# meteo-slave.net
KiCad netlist of a schematic drawn in EAGLE
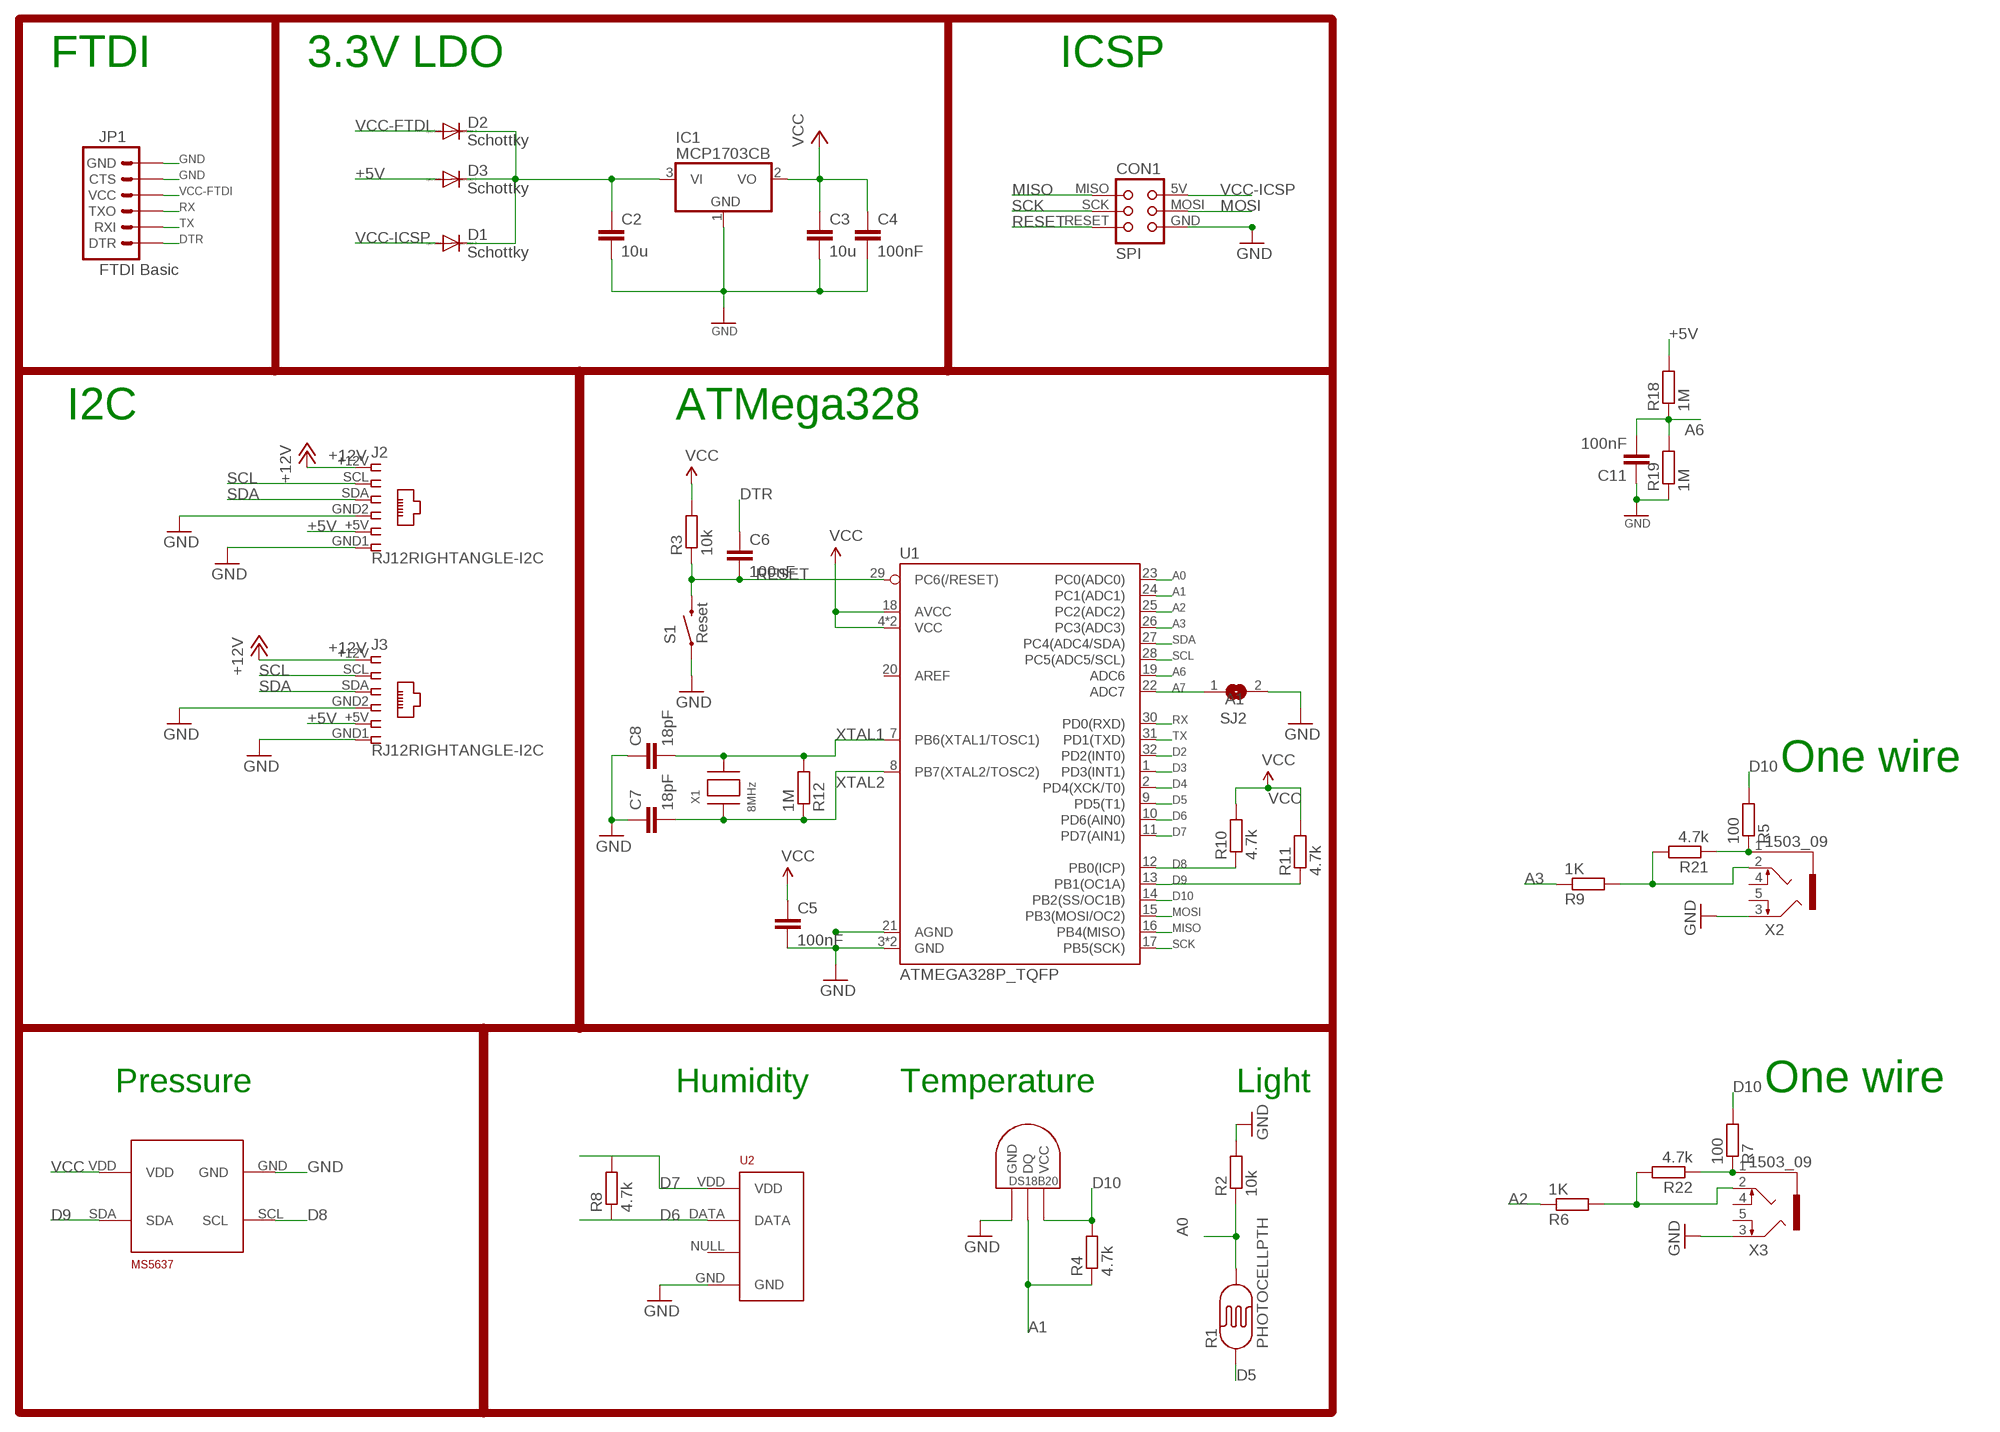
[diagram p0: schematic, sheet 1]

(export (version "E")
  (design (tool "Eeschema 10.0.6"))
  (components
    (comp (ref "C2")
      (value "10u")
      (footprint "eagle-import:C0805K")
      (fields (field (name "MPN") "77-VJ1206V106ZXQTBC"))
      (libsource (lib "eagle-import") (part "C-EUC0805K"))
    )
    (comp (ref "C3")
      (value "10u")
      (footprint "eagle-import:C0805K")
      (fields (field (name "MPN") "77-VJ1206V106ZXQTBC"))
      (libsource (lib "eagle-import") (part "C-EUC0805K"))
    )
    (comp (ref "C4")
      (value "100nF")
      (footprint "eagle-import:C0805K")
      (fields (field (name "MPN") "80-C1206C104K5R"))
      (libsource (lib "eagle-import") (part "C-EUC0805K"))
    )
    (comp (ref "C5")
      (value "100nF")
      (footprint "eagle-import:C0805K")
      (fields (field (name "MPN") "80-C1206C104K5R"))
      (libsource (lib "eagle-import") (part "C-EUC0805K"))
    )
    (comp (ref "C6")
      (value "100nF")
      (footprint "eagle-import:C0805K")
      (fields (field (name "MPN") "80-C1206C104K5R"))
      (libsource (lib "eagle-import") (part "C-EUC0805K"))
    )
    (comp (ref "C7")
      (value "18pF")
      (footprint "eagle-import:C0805K")
      (fields (field (name "MPN") "77-VJ1206A180JXXPBC"))
      (libsource (lib "eagle-import") (part "C-EUC0805K"))
    )
    (comp (ref "C8")
      (value "18pF")
      (footprint "eagle-import:C0805K")
      (fields (field (name "MPN") "77-VJ1206A180JXXPBC"))
      (libsource (lib "eagle-import") (part "C-EUC0805K"))
    )
    (comp (ref "C11")
      (value "100nF")
      (footprint "eagle-import:C0805K")
      (fields (field (name "MPN") "80-C1206C104K5R"))
      (libsource (lib "eagle-import") (part "C-EUC0805K"))
    )
    (comp (ref "CON1")
      (value "SPI")
      (footprint "eagle-import:TC2030-MCP")
      (libsource (lib "eagle-import") (part "TINYISPTAG"))
    )
    (comp (ref "D1")
      (value "Schottky")
      (footprint "eagle-import:SOD123")
      (fields (field (name "MPN") "621-1N5819HW-F"))
      (libsource (lib "eagle-import") (part "MBR0520LT"))
    )
    (comp (ref "D2")
      (value "Schottky")
      (footprint "eagle-import:SOD123")
      (fields (field (name "MPN") "621-1N5819HW-F"))
      (libsource (lib "eagle-import") (part "MBR0520LT"))
    )
    (comp (ref "D3")
      (value "Schottky")
      (footprint "eagle-import:SOD123")
      (fields (field (name "MPN") "621-1N5819HW-F"))
      (libsource (lib "eagle-import") (part "MBR0520LT"))
    )
    (comp (ref "IC1")
      (value "MCP1703CB")
      (footprint "eagle-import:SOT23")
      (libsource (lib "eagle-import") (part "MCP1703CB"))
    )
    (comp (ref "J2")
      (value "RJ12RIGHTANGLE-I2C")
      (footprint "eagle-import:RJ12-RIGHTANGLE-I2C")
      (libsource (lib "eagle-import") (part "RJ12RIGHTANGLE-I2C"))
    )
    (comp (ref "J3")
      (value "RJ12RIGHTANGLE-I2C")
      (footprint "eagle-import:RJ12-RIGHTANGLE-I2C")
      (libsource (lib "eagle-import") (part "RJ12RIGHTANGLE-I2C"))
    )
    (comp (ref "JP1")
      (value "FTDI Basic")
      (footprint "eagle-import:1X06")
      (libsource (lib "eagle-import") (part "ARDUINO_SERIAL_PROGRAMPTH"))
    )
    (comp (ref "R1")
      (value "PHOTOCELLPTH")
      (footprint "eagle-import:PHOTOCELL")
      (libsource (lib "eagle-import") (part "PHOTOCELLPTH"))
    )
    (comp (ref "R2")
      (value "10k")
      (footprint "eagle-import:R0805")
      (libsource (lib "eagle-import") (part "resistor_348_R-EU_R0805"))
    )
    (comp (ref "R3")
      (value "10k")
      (footprint "eagle-import:R0805")
      (libsource (lib "eagle-import") (part "R-EU_R0805"))
    )
    (comp (ref "R4")
      (value "4.7k")
      (footprint "eagle-import:R0805")
      (libsource (lib "eagle-import") (part "resistor_348_R-EU_R0805"))
    )
    (comp (ref "R5")
      (value "100")
      (footprint "eagle-import:R0805")
      (libsource (lib "eagle-import") (part "R-EU_R0805"))
    )
    (comp (ref "R6")
      (value "1K")
      (footprint "eagle-import:R0805")
      (libsource (lib "eagle-import") (part "R-EU_R0805"))
    )
    (comp (ref "R7")
      (value "100")
      (footprint "eagle-import:R0805")
      (libsource (lib "eagle-import") (part "R-EU_R0805"))
    )
    (comp (ref "R8")
      (value "4.7k")
      (footprint "eagle-import:R0805")
      (libsource (lib "eagle-import") (part "resistor_348_R-EU_R0805"))
    )
    (comp (ref "R9")
      (value "1K")
      (footprint "eagle-import:R0805")
      (libsource (lib "eagle-import") (part "R-EU_R0805"))
    )
    (comp (ref "R10")
      (value "4.7k")
      (footprint "eagle-import:R0805")
      (libsource (lib "eagle-import") (part "resistor_348_R-EU_R0805"))
    )
    (comp (ref "R11")
      (value "4.7k")
      (footprint "eagle-import:R0805")
      (libsource (lib "eagle-import") (part "resistor_348_R-EU_R0805"))
    )
    (comp (ref "R12")
      (value "1M")
      (footprint "eagle-import:R0805")
      (libsource (lib "eagle-import") (part "R-EU_R0805"))
    )
    (comp (ref "R18")
      (value "1M")
      (footprint "eagle-import:R0805")
      (libsource (lib "eagle-import") (part "R-EU_R0805"))
    )
    (comp (ref "R19")
      (value "1M")
      (footprint "eagle-import:R0805")
      (libsource (lib "eagle-import") (part "R-EU_R0805"))
    )
    (comp (ref "R21")
      (value "4.7k")
      (footprint "eagle-import:R0805")
      (libsource (lib "eagle-import") (part "resistor_R-EU_R0805"))
    )
    (comp (ref "R22")
      (value "4.7k")
      (footprint "eagle-import:R0805")
      (libsource (lib "eagle-import") (part "resistor_R-EU_R0805"))
    )
    (comp (ref "S1")
      (value "Reset")
      (footprint "eagle-import:TACTILE-SWITCH-SMD-ALT01")
      (libsource (lib "eagle-import") (part "SWITCH-MOMENTARY-2SMD-ALT01"))
    )
    (comp (ref "SJ2") (value "A1") (footprint "eagle-import:SJ") (libsource (lib "eagle-import") (part "SJ")))
    (comp (ref "U$1")
      (value "DS1820TO92")
      (footprint "eagle-import:DS1820")
      (libsource (lib "eagle-import") (part "DS1820TO92"))
    )
    (comp (ref "U$19")
      (value "MS5637WIDE")
      (footprint "eagle-import:MS5637WIDE")
      (libsource (lib "eagle-import") (part "MS5637WIDE"))
    )
    (comp (ref "U1")
      (value "ATMEGA328P_TQFP")
      (footprint "eagle-import:TQFP32-08")
      (libsource (lib "eagle-import") (part "ATMEGA328P_TQFP"))
    )
    (comp (ref "U2")
      (value "RHT03_DHT-22_AM2302")
      (footprint "eagle-import:RHT03_DHT-22")
      (libsource (lib "eagle-import") (part "RHT03_DHT-22_AM2302"))
    )
    (comp (ref "X1")
      (value "8MHz")
      (footprint "eagle-import:NX6035")
      (fields (field (name "MPN") "729-F60800010"))
      (libsource (lib "eagle-import") (part "XTALNX6035"))
    )
    (comp (ref "X2")
      (value "1503_09")
      (footprint "eagle-import:1503_09")
      (libsource (lib "eagle-import") (part "1503_09"))
    )
    (comp (ref "X3")
      (value "1503_09")
      (footprint "eagle-import:1503_09")
      (libsource (lib "eagle-import") (part "1503_09"))
    )
  )
  (nets
    (net (code "1") (name "+5V") (class "Default")
      (node (ref "D3") (pin "A") (pinfunction "A_A") (pintype "passive"))
      (node (ref "J2") (pin "+5V") (pinfunction "5_+5V") (pintype "bidirectional"))
      (node (ref "J3") (pin "+5V") (pinfunction "5_+5V") (pintype "bidirectional"))
      (node (ref "R18") (pin "2") (pinfunction "2_2") (pintype "passive"))
    )
    (net (code "2") (name "+12V") (class "Default")
      (node (ref "J2") (pin "+12V") (pinfunction "1_+12V") (pintype "bidirectional"))
      (node (ref "J3") (pin "+12V") (pinfunction "1_+12V") (pintype "bidirectional"))
    )
    (net (code "3") (name "A0") (class "Default")
      (node (ref "R1") (pin "2") (pinfunction "P$2_2") (pintype "bidirectional"))
      (node (ref "R2") (pin "1") (pinfunction "1_1") (pintype "passive"))
      (node (ref "U1") (pin "23") (pinfunction "PC0(ADC0)_23") (pintype "bidirectional"))
    )
    (net (code "4") (name "A1") (class "Default")
      (node (ref "R4") (pin "1") (pinfunction "1_1") (pintype "passive"))
      (node (ref "U$1") (pin "DQ") (pinfunction "DQ_DQ") (pintype "bidirectional"))
      (node (ref "U1") (pin "24") (pinfunction "PC1(ADC1)_24") (pintype "bidirectional"))
    )
    (net (code "5") (name "A2") (class "Default")
      (node (ref "R6") (pin "1") (pinfunction "1_1") (pintype "passive"))
      (node (ref "U1") (pin "25") (pinfunction "PC2(ADC2)_25") (pintype "bidirectional"))
    )
    (net (code "6") (name "A3") (class "Default")
      (node (ref "R9") (pin "1") (pinfunction "1_1") (pintype "passive"))
      (node (ref "U1") (pin "26") (pinfunction "PC3(ADC3)_26") (pintype "bidirectional"))
    )
    (net (code "7") (name "A6") (class "Default")
      (node (ref "C11") (pin "2") (pinfunction "2_2") (pintype "passive"))
      (node (ref "R18") (pin "1") (pinfunction "1_1") (pintype "passive"))
      (node (ref "R19") (pin "2") (pinfunction "2_2") (pintype "passive"))
      (node (ref "U1") (pin "19") (pinfunction "ADC6_19") (pintype "bidirectional"))
    )
    (net (code "8") (name "A7") (class "Default")
      (node (ref "SJ2") (pin "1") (pinfunction "1_1") (pintype "passive"))
      (node (ref "U1") (pin "22") (pinfunction "ADC7_22") (pintype "bidirectional"))
    )
    (net (code "9") (name "D2") (class "Default")
      (node (ref "U1") (pin "32") (pinfunction "PD2(INT0)_32") (pintype "bidirectional"))
    )
    (net (code "10") (name "D3") (class "Default")
      (node (ref "U1") (pin "1") (pinfunction "PD3(INT1)_1") (pintype "bidirectional"))
    )
    (net (code "11") (name "D4") (class "Default")
      (node (ref "U1") (pin "2") (pinfunction "PD4(XCK/T0)_2") (pintype "bidirectional"))
    )
    (net (code "12") (name "D5") (class "Default")
      (node (ref "R1") (pin "1") (pinfunction "P$1_1") (pintype "bidirectional"))
      (node (ref "U1") (pin "9") (pinfunction "PD5(T1)_9") (pintype "bidirectional"))
    )
    (net (code "13") (name "D6") (class "Default")
      (node (ref "R8") (pin "1") (pinfunction "1_1") (pintype "passive"))
      (node (ref "U1") (pin "10") (pinfunction "PD6(AIN0)_10") (pintype "bidirectional"))
      (node (ref "U2") (pin "DATA") (pinfunction "DATA_DATA") (pintype "bidirectional"))
    )
    (net (code "14") (name "D7") (class "Default")
      (node (ref "R8") (pin "2") (pinfunction "2_2") (pintype "passive"))
      (node (ref "U1") (pin "11") (pinfunction "PD7(AIN1)_11") (pintype "bidirectional"))
      (node (ref "U2") (pin "VDD") (pinfunction "VDD_VDD") (pintype "power_in"))
    )
    (net (code "15") (name "D8") (class "Default")
      (node (ref "R10") (pin "1") (pinfunction "1_1") (pintype "passive"))
      (node (ref "U$19") (pin "SCL") (pinfunction "SCL_SCL") (pintype "bidirectional"))
      (node (ref "U1") (pin "12") (pinfunction "PB0(ICP)_12") (pintype "bidirectional"))
    )
    (net (code "16") (name "D9") (class "Default")
      (node (ref "R11") (pin "1") (pinfunction "1_1") (pintype "passive"))
      (node (ref "U$19") (pin "SDA") (pinfunction "SDA_SDA") (pintype "bidirectional"))
      (node (ref "U1") (pin "13") (pinfunction "PB1(OC1A)_13") (pintype "bidirectional"))
    )
    (net (code "17") (name "D10") (class "Default")
      (node (ref "R4") (pin "2") (pinfunction "2_2") (pintype "passive"))
      (node (ref "R5") (pin "2") (pinfunction "2_2") (pintype "passive"))
      (node (ref "R7") (pin "2") (pinfunction "2_2") (pintype "passive"))
      (node (ref "U$1") (pin "VDD") (pinfunction "VCC_VDD") (pintype "power_in"))
      (node (ref "U1") (pin "14") (pinfunction "PB2(SS/OC1B)_14") (pintype "bidirectional"))
    )
    (net (code "18") (name "DTR") (class "Default")
      (node (ref "C6") (pin "1") (pinfunction "1_1") (pintype "passive"))
      (node (ref "JP1") (pin "1") (pinfunction "DTR_1") (pintype "passive"))
    )
    (net (code "19") (name "GND") (class "Default")
      (node (ref "C11") (pin "1") (pinfunction "1_1") (pintype "passive"))
      (node (ref "C2") (pin "2") (pinfunction "2_2") (pintype "passive"))
      (node (ref "C3") (pin "2") (pinfunction "2_2") (pintype "passive"))
      (node (ref "C4") (pin "2") (pinfunction "2_2") (pintype "passive"))
      (node (ref "C5") (pin "2") (pinfunction "2_2") (pintype "passive"))
      (node (ref "C7") (pin "1") (pinfunction "1_1") (pintype "passive"))
      (node (ref "C8") (pin "1") (pinfunction "1_1") (pintype "passive"))
      (node (ref "CON1") (pin "GND") (pinfunction "GND_GND") (pintype "passive"))
      (node (ref "IC1") (pin "1") (pinfunction "GND_1") (pintype "passive"))
      (node (ref "J2") (pin "GND1") (pinfunction "6_GND1") (pintype "bidirectional"))
      (node (ref "J2") (pin "GND2") (pinfunction "4_GND2") (pintype "bidirectional"))
      (node (ref "J3") (pin "GND1") (pinfunction "6_GND1") (pintype "bidirectional"))
      (node (ref "J3") (pin "GND2") (pinfunction "4_GND2") (pintype "bidirectional"))
      (node (ref "JP1") (pin "5") (pinfunction "CTS_5") (pintype "passive"))
      (node (ref "JP1") (pin "6") (pinfunction "GND_6") (pintype "passive"))
      (node (ref "R19") (pin "1") (pinfunction "1_1") (pintype "passive"))
      (node (ref "R2") (pin "2") (pinfunction "2_2") (pintype "passive"))
      (node (ref "S1") (pin "1") (pinfunction "1_1") (pintype "passive"))
      (node (ref "S1") (pin "2") (pinfunction "1_2") (pintype "passive"))
      (node (ref "SJ2") (pin "2") (pinfunction "2_2") (pintype "passive"))
      (node (ref "U$1") (pin "GND") (pinfunction "GND_GND") (pintype "power_in"))
      (node (ref "U$19") (pin "GND") (pinfunction "GND_GND") (pintype "bidirectional"))
      (node (ref "U1") (pin "21") (pinfunction "AGND_21") (pintype "bidirectional"))
      (node (ref "U1") (pin "3") (pinfunction "GND_3") (pintype "bidirectional"))
      (node (ref "U1") (pin "5") (pinfunction "GND_5") (pintype "bidirectional"))
      (node (ref "U2") (pin "GND") (pinfunction "GND_GND") (pintype "power_in"))
      (node (ref "X2") (pin "3") (pinfunction "3_3") (pintype "passive"))
      (node (ref "X3") (pin "3") (pinfunction "3_3") (pintype "passive"))
    )
    (net (code "20") (name "MISO") (class "Default")
      (node (ref "CON1") (pin "MISO") (pinfunction "MISO_MISO") (pintype "passive"))
      (node (ref "U1") (pin "16") (pinfunction "PB4(MISO)_16") (pintype "bidirectional"))
    )
    (net (code "21") (name "MOSI") (class "Default")
      (node (ref "CON1") (pin "MOSI") (pinfunction "MOSI_MOSI") (pintype "passive"))
      (node (ref "U1") (pin "15") (pinfunction "PB3(MOSI/OC2)_15") (pintype "bidirectional"))
    )
    (net (code "22") (name "Net-(IC1-VI)") (class "Default")
      (node (ref "C2") (pin "1") (pinfunction "1_1") (pintype "passive"))
      (node (ref "D1") (pin "C") (pinfunction "C_C") (pintype "passive"))
      (node (ref "D2") (pin "C") (pinfunction "C_C") (pintype "passive"))
      (node (ref "D3") (pin "C") (pinfunction "C_C") (pintype "passive"))
      (node (ref "IC1") (pin "3") (pinfunction "VI_3") (pintype "input"))
    )
    (net (code "23") (name "Net-(R21-Pad1)") (class "Default")
      (node (ref "R21") (pin "1") (pinfunction "1_1") (pintype "passive"))
      (node (ref "R5") (pin "1") (pinfunction "1_1") (pintype "passive"))
      (node (ref "X2") (pin "1") (pinfunction "1_1") (pintype "passive"))
    )
    (net (code "24") (name "Net-(R21-Pad2)") (class "Default")
      (node (ref "R21") (pin "2") (pinfunction "2_2") (pintype "passive"))
      (node (ref "R9") (pin "2") (pinfunction "2_2") (pintype "passive"))
      (node (ref "X2") (pin "2") (pinfunction "2_2") (pintype "passive"))
    )
    (net (code "25") (name "Net-(R22-Pad1)") (class "Default")
      (node (ref "R22") (pin "1") (pinfunction "1_1") (pintype "passive"))
      (node (ref "R7") (pin "1") (pinfunction "1_1") (pintype "passive"))
      (node (ref "X3") (pin "1") (pinfunction "1_1") (pintype "passive"))
    )
    (net (code "26") (name "Net-(R22-Pad2)") (class "Default")
      (node (ref "R22") (pin "2") (pinfunction "2_2") (pintype "passive"))
      (node (ref "R6") (pin "2") (pinfunction "2_2") (pintype "passive"))
      (node (ref "X3") (pin "2") (pinfunction "2_2") (pintype "passive"))
    )
    (net (code "27") (name "RESET") (class "Default")
      (node (ref "C6") (pin "2") (pinfunction "2_2") (pintype "passive"))
      (node (ref "CON1") (pin "RESET") (pinfunction "RESET_RESET") (pintype "passive"))
      (node (ref "R3") (pin "1") (pinfunction "1_1") (pintype "passive"))
      (node (ref "S1") (pin "3") (pinfunction "2_3") (pintype "passive"))
      (node (ref "S1") (pin "4") (pinfunction "2_4") (pintype "passive"))
      (node (ref "U1") (pin "29") (pinfunction "PC6(/RESET)_29") (pintype "bidirectional"))
    )
    (net (code "28") (name "RX") (class "Default")
      (node (ref "JP1") (pin "3") (pinfunction "TXO_3") (pintype "passive"))
      (node (ref "U1") (pin "30") (pinfunction "PD0(RXD)_30") (pintype "bidirectional"))
    )
    (net (code "29") (name "SCK") (class "Default")
      (node (ref "CON1") (pin "SCK") (pinfunction "SCK_SCK") (pintype "passive"))
      (node (ref "U1") (pin "17") (pinfunction "PB5(SCK)_17") (pintype "bidirectional"))
    )
    (net (code "30") (name "SCL") (class "Default")
      (node (ref "J2") (pin "SCL") (pinfunction "2_SCL") (pintype "bidirectional"))
      (node (ref "J3") (pin "SCL") (pinfunction "2_SCL") (pintype "bidirectional"))
      (node (ref "U1") (pin "28") (pinfunction "PC5(ADC5/SCL)_28") (pintype "bidirectional"))
    )
    (net (code "31") (name "SDA") (class "Default")
      (node (ref "J2") (pin "SDA") (pinfunction "3_SDA") (pintype "bidirectional"))
      (node (ref "J3") (pin "SDA") (pinfunction "3_SDA") (pintype "bidirectional"))
      (node (ref "U1") (pin "27") (pinfunction "PC4(ADC4/SDA)_27") (pintype "bidirectional"))
    )
    (net (code "32") (name "TX") (class "Default")
      (node (ref "JP1") (pin "2") (pinfunction "RXI_2") (pintype "passive"))
      (node (ref "U1") (pin "31") (pinfunction "PD1(TXD)_31") (pintype "bidirectional"))
    )
    (net (code "33") (name "VCC") (class "Default")
      (node (ref "C3") (pin "1") (pinfunction "1_1") (pintype "passive"))
      (node (ref "C4") (pin "1") (pinfunction "1_1") (pintype "passive"))
      (node (ref "C5") (pin "1") (pinfunction "1_1") (pintype "passive"))
      (node (ref "IC1") (pin "2") (pinfunction "VO_2") (pintype "passive"))
      (node (ref "R10") (pin "2") (pinfunction "2_2") (pintype "passive"))
      (node (ref "R11") (pin "2") (pinfunction "2_2") (pintype "passive"))
      (node (ref "R3") (pin "2") (pinfunction "2_2") (pintype "passive"))
      (node (ref "U$19") (pin "VDD") (pinfunction "VDD_VDD") (pintype "bidirectional"))
      (node (ref "U1") (pin "18") (pinfunction "AVCC_18") (pintype "bidirectional"))
      (node (ref "U1") (pin "4") (pinfunction "VCC_4") (pintype "bidirectional"))
      (node (ref "U1") (pin "6") (pinfunction "VCC_6") (pintype "bidirectional"))
    )
    (net (code "34") (name "VCC-FTDI") (class "Default")
      (node (ref "D2") (pin "A") (pinfunction "A_A") (pintype "passive"))
      (node (ref "JP1") (pin "4") (pinfunction "VCC_4") (pintype "passive"))
    )
    (net (code "35") (name "VCC-ICSP") (class "Default")
      (node (ref "CON1") (pin "5V") (pinfunction "VCC_5V") (pintype "passive"))
      (node (ref "D1") (pin "A") (pinfunction "A_A") (pintype "passive"))
    )
    (net (code "36") (name "XTAL1") (class "Default")
      (node (ref "C8") (pin "2") (pinfunction "2_2") (pintype "passive"))
      (node (ref "R12") (pin "2") (pinfunction "2_2") (pintype "passive"))
      (node (ref "U1") (pin "7") (pinfunction "PB6(XTAL1/TOSC1)_7") (pintype "bidirectional"))
      (node (ref "X1") (pin "P$2") (pinfunction "P$2_P$2") (pintype "bidirectional"))
    )
    (net (code "37") (name "XTAL2") (class "Default")
      (node (ref "C7") (pin "2") (pinfunction "2_2") (pintype "passive"))
      (node (ref "R12") (pin "1") (pinfunction "1_1") (pintype "passive"))
      (node (ref "U1") (pin "8") (pinfunction "PB7(XTAL2/TOSC2)_8") (pintype "bidirectional"))
      (node (ref "X1") (pin "P$1") (pinfunction "P$1_P$1") (pintype "bidirectional"))
    )
    (net (code "38") (name "unconnected-(U1-AREF-Pad20)") (class "Default")
      (node (ref "U1") (pin "20") (pinfunction "AREF_20") (pintype "bidirectional"))
    )
    (net (code "39") (name "unconnected-(U2-PadNULL)") (class "Default")
      (node (ref "U2") (pin "NULL") (pinfunction "NULL_NULL") (pintype "no_connect"))
    )
    (net (code "40") (name "unconnected-(X2-Pad4)") (class "Default")
      (node (ref "X2") (pin "4") (pinfunction "4_4") (pintype "passive"))
    )
    (net (code "41") (name "unconnected-(X2-Pad5)") (class "Default")
      (node (ref "X2") (pin "5") (pinfunction "5_5") (pintype "passive"))
    )
    (net (code "42") (name "unconnected-(X3-Pad4)") (class "Default")
      (node (ref "X3") (pin "4") (pinfunction "4_4") (pintype "passive"))
    )
    (net (code "43") (name "unconnected-(X3-Pad5)") (class "Default")
      (node (ref "X3") (pin "5") (pinfunction "5_5") (pintype "passive"))
    )
  )
)
